# Power.net
KiCad netlist of a schematic drawn in Altium Designer
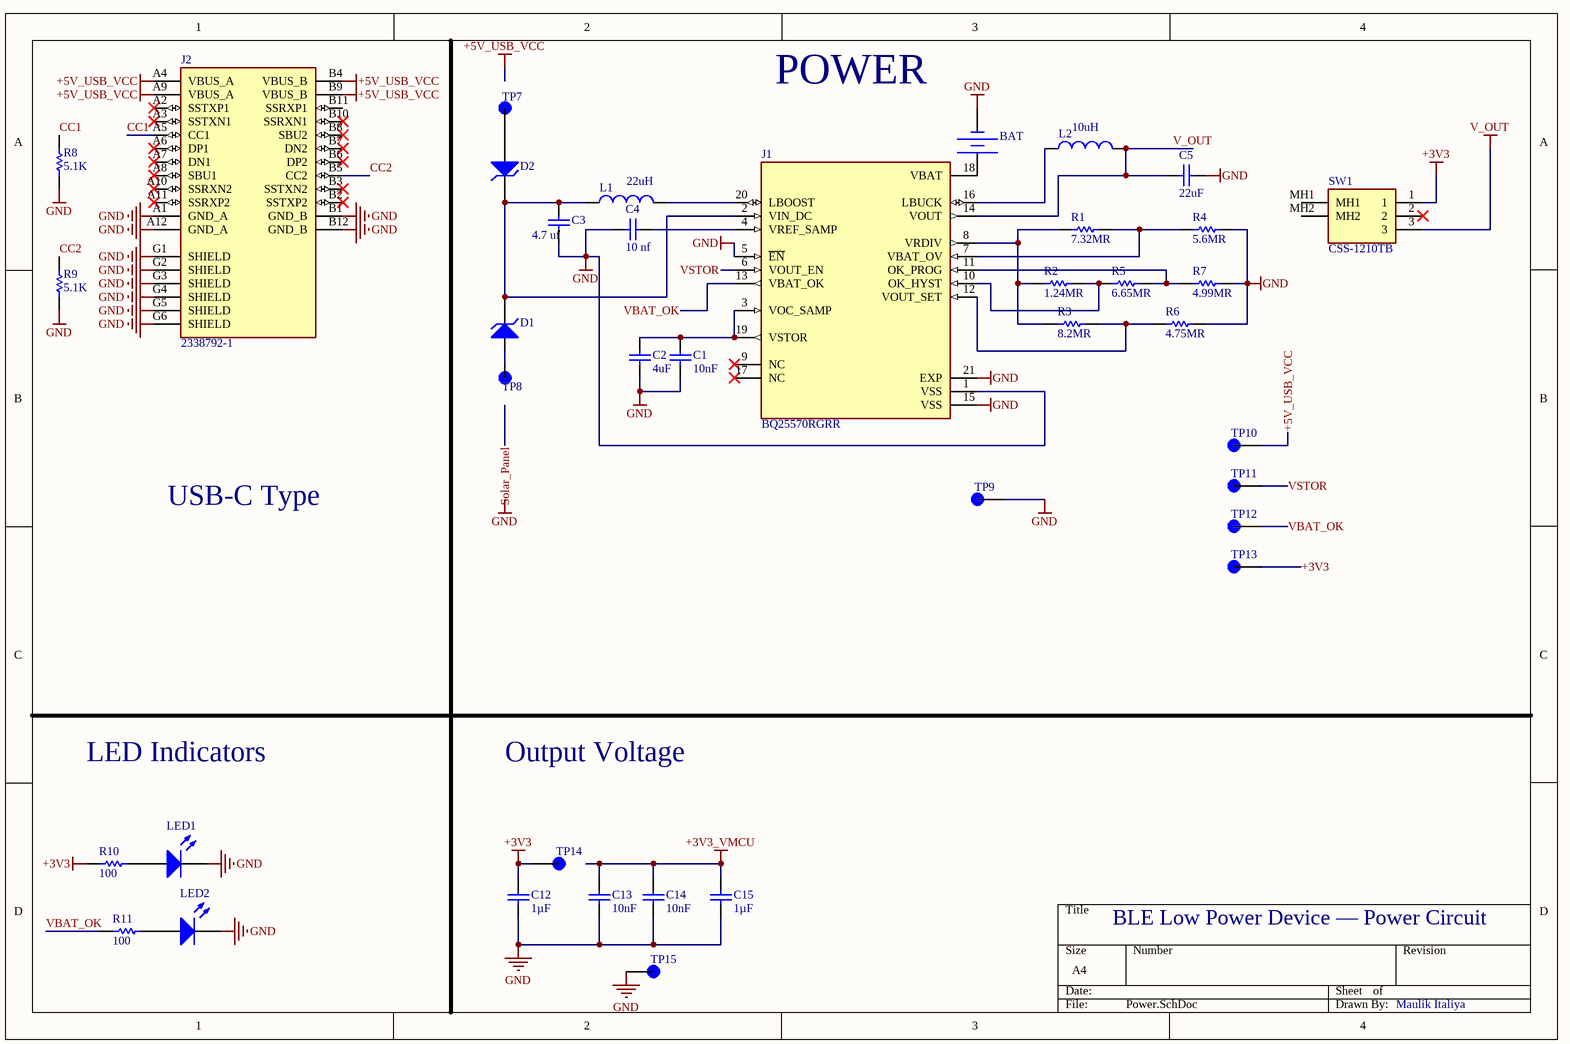
[diagram p0: Power.SchDoc]

(export (version "E")
  (design (tool "Eeschema 10.0.6"))
  (components
    (comp (ref "BAT")
      (value "Constant Voltage Source")
      (libsource (lib "Simulation Generic Components") (part "Battery"))
    )
    (comp (ref "C1")
      (value "10nF")
      (description "Capacitor")
      (libsource (lib "Simulation Generic Components") (part "Capacitor"))
    )
    (comp (ref "C2")
      (value "4uF")
      (description "Capacitor")
      (libsource (lib "Simulation Generic Components") (part "Capacitor"))
    )
    (comp (ref "C3")
      (value "4.7 uf")
      (description "Capacitor")
      (libsource (lib "Simulation Generic Components") (part "Capacitor"))
    )
    (comp (ref "C4")
      (value "10 nf")
      (description "Capacitor")
      (libsource (lib "Simulation Generic Components") (part "Capacitor"))
    )
    (comp (ref "C5")
      (value "22uF")
      (description "Capacitor")
      (libsource (lib "Simulation Generic Components") (part "Capacitor"))
    )
    (comp (ref "C12")
      (value "1µF")
      (description "Capacitor")
      (libsource (lib "Simulation Generic Components") (part "Capacitor"))
    )
    (comp (ref "C13")
      (value "10nF")
      (description "Capacitor")
      (libsource (lib "Simulation Generic Components") (part "Capacitor"))
    )
    (comp (ref "C14")
      (value "10nF")
      (description "Capacitor")
      (libsource (lib "Simulation Generic Components") (part "Capacitor"))
    )
    (comp (ref "C15")
      (value "1µF")
      (description "Capacitor")
      (libsource (lib "Simulation Generic Components") (part "Capacitor"))
    )
    (comp (ref "D1")
      (value "Zener Diode")
      (libsource (lib "Simulation Generic Components") (part "Zener Diode"))
    )
    (comp (ref "D2")
      (value "Zener Diode")
      (libsource (lib "Simulation Generic Components") (part "Zener Diode"))
    )
    (comp (ref "J1")
      (value "BQ25570RGRR")
      (footprint "QFN50P350X350X100-21N")
      (description "Ultra Low power Harvester power Management IC with boost charger, and Nanopower Buck Converter")
      (fields (field (name "MF") "Texas Instruments"))
      (libsource (lib "BQ25570RGRR") (part "BQ25570RGRR"))
    )
    (comp (ref "J2")
      (value "2338792-1")
      (footprint "TE_2338792-1")
      (description "USB TYPE C 3.1 CONN REV TOP MOUNT CH1.6")
      (fields (field (name "MF") "TE Connectivity"))
      (libsource (lib "2338792-1") (part "2338792-1"))
    )
    (comp (ref "L1")
      (value "22uH")
      (description "Inductor")
      (libsource (lib "Simulation Generic Components") (part "Inductor"))
    )
    (comp (ref "L2")
      (value "10uH")
      (description "Inductor")
      (libsource (lib "Simulation Generic Components") (part "Inductor"))
    )
    (comp (ref "LED1")
      (value "Green")
      (description "Light-Emitting Diode")
      (libsource (lib "Simulation Generic Components") (part "LED"))
    )
    (comp (ref "LED2")
      (value "Light-Emitting Diode")
      (libsource (lib "Simulation Generic Components") (part "LED"))
    )
    (comp (ref "R1")
      (value "7.32MR")
      (description "Resistor")
      (libsource (lib "Simulation Generic Components") (part "Resistor"))
    )
    (comp (ref "R2")
      (value "1.24MR")
      (description "Resistor")
      (libsource (lib "Simulation Generic Components") (part "Resistor"))
    )
    (comp (ref "R3")
      (value "8.2MR")
      (description "Resistor")
      (libsource (lib "Simulation Generic Components") (part "Resistor"))
    )
    (comp (ref "R4")
      (value "5.6MR")
      (description "Resistor")
      (libsource (lib "Simulation Generic Components") (part "Resistor"))
    )
    (comp (ref "R5")
      (value "6.65MR")
      (description "Resistor")
      (libsource (lib "Simulation Generic Components") (part "Resistor"))
    )
    (comp (ref "R6")
      (value "4.75MR")
      (description "Resistor")
      (libsource (lib "Simulation Generic Components") (part "Resistor"))
    )
    (comp (ref "R7")
      (value "4.99MR")
      (description "Resistor")
      (libsource (lib "Simulation Generic Components") (part "Resistor"))
    )
    (comp (ref "R8")
      (value "5.1K")
      (description "Resistor")
      (libsource (lib "Simulation Generic Components") (part "Resistor"))
    )
    (comp (ref "R9")
      (value "5.1K")
      (description "Resistor")
      (libsource (lib "Simulation Generic Components") (part "Resistor"))
    )
    (comp (ref "R10")
      (value "100")
      (description "Resistor")
      (libsource (lib "Simulation Generic Components") (part "Resistor"))
    )
    (comp (ref "R11")
      (value "100")
      (description "Resistor")
      (libsource (lib "Simulation Generic Components") (part "Resistor"))
    )
    (comp (ref "SW1")
      (value "CSS-1210TB")
      (footprint "CSS1210TB")
      (description "SWITCH SLIDE SPDT 100MA 12V")
      (fields (field (name "MOUSER PART NUMBER") "229-CSS-1210TB"))
      (libsource (lib "CSS-1210TB") (part "CSS-1210TB"))
    )
    (comp (ref "TP7")
      (value "~")
      (footprint "KEYSTONE_5003")
      (fields (field (name "MF") "Keystone Electronics Corp.") (field (name "MP") "5003"))
      (libsource (lib "5003") (part "5003"))
    )
    (comp (ref "TP8")
      (value "~")
      (footprint "KEYSTONE_5003")
      (fields (field (name "MF") "Keystone Electronics Corp.") (field (name "MP") "5003"))
      (libsource (lib "5003") (part "5003"))
    )
    (comp (ref "TP9")
      (value "~")
      (footprint "KEYSTONE_5003")
      (fields (field (name "MF") "Keystone Electronics Corp.") (field (name "MP") "5003"))
      (libsource (lib "5003") (part "5003"))
    )
    (comp (ref "TP10")
      (value "~")
      (footprint "KEYSTONE_5003")
      (fields (field (name "MF") "Keystone Electronics Corp.") (field (name "MP") "5003"))
      (libsource (lib "5003") (part "5003"))
    )
    (comp (ref "TP11")
      (value "~")
      (footprint "KEYSTONE_5003")
      (fields (field (name "MF") "Keystone Electronics Corp.") (field (name "MP") "5003"))
      (libsource (lib "5003") (part "5003"))
    )
    (comp (ref "TP12")
      (value "~")
      (footprint "KEYSTONE_5003")
      (fields (field (name "MF") "Keystone Electronics Corp.") (field (name "MP") "5003"))
      (libsource (lib "5003") (part "5003"))
    )
    (comp (ref "TP13")
      (value "~")
      (footprint "KEYSTONE_5003")
      (fields (field (name "MF") "Keystone Electronics Corp.") (field (name "MP") "5003"))
      (libsource (lib "5003") (part "5003"))
    )
    (comp (ref "TP14")
      (value "~")
      (footprint "KEYSTONE_5003")
      (fields (field (name "MF") "Keystone Electronics Corp.") (field (name "MP") "5003"))
      (libsource (lib "5003") (part "5003"))
    )
    (comp (ref "TP15")
      (value "~")
      (footprint "KEYSTONE_5003")
      (fields (field (name "MF") "Keystone Electronics Corp.") (field (name "MP") "5003"))
      (libsource (lib "5003") (part "5003"))
    )
  )
  (nets
    (net (code "1") (name "+3V3") (class "Default")
      (node (ref "C12") (pin "1") (pinfunction "1_1") (pintype "passive"))
      (node (ref "R10") (pin "2") (pinfunction "2_2") (pintype "passive"))
      (node (ref "SW1") (pin "1") (pinfunction "1_1") (pintype "passive"))
      (node (ref "TP13") (pin "TP") (pinfunction "TP_TP") (pintype "passive"))
      (node (ref "TP14") (pin "TP") (pinfunction "TP_TP") (pintype "passive"))
    )
    (net (code "2") (name "+3V3_VMCU") (class "Default")
      (node (ref "C13") (pin "1") (pinfunction "1_1") (pintype "passive"))
      (node (ref "C14") (pin "1") (pinfunction "1_1") (pintype "passive"))
      (node (ref "C15") (pin "1") (pinfunction "1_1") (pintype "passive"))
    )
    (net (code "3") (name "+5V_USB_VCC") (class "Default")
      (node (ref "J2") (pin "A4") (pinfunction "VBUS_A_A4") (pintype "power_in"))
      (node (ref "J2") (pin "A9") (pinfunction "VBUS_A_A9") (pintype "power_in"))
      (node (ref "J2") (pin "B4") (pinfunction "VBUS_B_B4") (pintype "power_in"))
      (node (ref "J2") (pin "B9") (pinfunction "VBUS_B_B9") (pintype "power_in"))
      (node (ref "TP10") (pin "TP") (pinfunction "TP_TP") (pintype "passive"))
    )
    (net (code "4") (name "/CC1") (class "Default")
      (node (ref "J2") (pin "A5") (pinfunction "CC1_A5") (pintype "bidirectional"))
      (node (ref "R8") (pin "2") (pinfunction "2_2") (pintype "passive"))
    )
    (net (code "5") (name "/CC2") (class "Default")
      (node (ref "J2") (pin "B5") (pinfunction "CC2_B5") (pintype "bidirectional"))
      (node (ref "R9") (pin "2") (pinfunction "2_2") (pintype "passive"))
    )
    (net (code "7") (name "/VBAT_OK") (class "Default")
      (node (ref "J1") (pin "13") (pinfunction "VBAT_OK_13") (pintype "output"))
      (node (ref "R11") (pin "2") (pinfunction "2_2") (pintype "passive"))
      (node (ref "TP12") (pin "TP") (pinfunction "TP_TP") (pintype "passive"))
    )
    (net (code "8") (name "/VSTOR") (class "Default")
      (node (ref "J1") (pin "6") (pinfunction "VOUT_EN_6") (pintype "input"))
      (node (ref "TP11") (pin "TP") (pinfunction "TP_TP") (pintype "passive"))
    )
    (net (code "9") (name "GND") (class "Default")
      (node (ref "BAT") (pin "2") (pinfunction "2_2") (pintype "passive"))
      (node (ref "C1") (pin "1") (pinfunction "1_1") (pintype "passive"))
      (node (ref "C12") (pin "2") (pinfunction "2_2") (pintype "passive"))
      (node (ref "C13") (pin "2") (pinfunction "2_2") (pintype "passive"))
      (node (ref "C14") (pin "2") (pinfunction "2_2") (pintype "passive"))
      (node (ref "C15") (pin "2") (pinfunction "2_2") (pintype "passive"))
      (node (ref "C2") (pin "1") (pinfunction "1_1") (pintype "passive"))
      (node (ref "C3") (pin "1") (pinfunction "1_1") (pintype "passive"))
      (node (ref "C4") (pin "2") (pinfunction "2_2") (pintype "passive"))
      (node (ref "C5") (pin "2") (pinfunction "2_2") (pintype "passive"))
      (node (ref "J1") (pin "1") (pinfunction "VSS_1") (pintype "power_in"))
      (node (ref "J1") (pin "15") (pinfunction "VSS_15") (pintype "power_in"))
      (node (ref "J1") (pin "21") (pinfunction "EXP_21") (pintype "passive"))
      (node (ref "J1") (pin "5") (pinfunction "~{EN}_5") (pintype "input"))
      (node (ref "J2") (pin "A1") (pinfunction "GND_A_A1") (pintype "power_in"))
      (node (ref "J2") (pin "A12") (pinfunction "GND_A_A12") (pintype "power_in"))
      (node (ref "J2") (pin "B1") (pinfunction "GND_B_B1") (pintype "power_in"))
      (node (ref "J2") (pin "B12") (pinfunction "GND_B_B12") (pintype "power_in"))
      (node (ref "J2") (pin "G1") (pinfunction "SHIELD_G1") (pintype "passive"))
      (node (ref "J2") (pin "G2") (pinfunction "SHIELD_G2") (pintype "passive"))
      (node (ref "J2") (pin "G3") (pinfunction "SHIELD_G3") (pintype "passive"))
      (node (ref "J2") (pin "G4") (pinfunction "SHIELD_G4") (pintype "passive"))
      (node (ref "J2") (pin "G5") (pinfunction "SHIELD_G5") (pintype "passive"))
      (node (ref "J2") (pin "G6") (pinfunction "SHIELD_G6") (pintype "passive"))
      (node (ref "LED1") (pin "2") (pinfunction "K_2") (pintype "passive"))
      (node (ref "LED2") (pin "2") (pinfunction "K_2") (pintype "passive"))
      (node (ref "R4") (pin "2") (pinfunction "2_2") (pintype "passive"))
      (node (ref "R6") (pin "2") (pinfunction "2_2") (pintype "passive"))
      (node (ref "R7") (pin "2") (pinfunction "2_2") (pintype "passive"))
      (node (ref "R8") (pin "1") (pinfunction "1_1") (pintype "passive"))
      (node (ref "R9") (pin "1") (pinfunction "1_1") (pintype "passive"))
      (node (ref "TP15") (pin "TP") (pinfunction "TP_TP") (pintype "passive"))
      (node (ref "TP9") (pin "TP") (pinfunction "TP_TP") (pintype "passive"))
    )
    (net (code "10") (name "Net-(D1-A)") (class "Default")
      (node (ref "D1") (pin "1") (pinfunction "A_1") (pintype "passive"))
      (node (ref "TP8") (pin "TP") (pinfunction "TP_TP") (pintype "passive"))
    )
    (net (code "11") (name "Net-(D1-K)") (class "Default")
      (node (ref "C3") (pin "2") (pinfunction "2_2") (pintype "passive"))
      (node (ref "D1") (pin "2") (pinfunction "K_2") (pintype "passive"))
      (node (ref "D2") (pin "2") (pinfunction "K_2") (pintype "passive"))
      (node (ref "J1") (pin "2") (pinfunction "VIN_DC_2") (pintype "input"))
      (node (ref "L1") (pin "1") (pinfunction "1_1") (pintype "passive"))
    )
    (net (code "12") (name "Net-(D2-A)") (class "Default")
      (node (ref "D2") (pin "1") (pinfunction "A_1") (pintype "passive"))
      (node (ref "TP7") (pin "TP") (pinfunction "TP_TP") (pintype "passive"))
    )
    (net (code "13") (name "Net-(J1-LBOOST)") (class "Default")
      (node (ref "J1") (pin "20") (pinfunction "LBOOST_20") (pintype "bidirectional"))
      (node (ref "L1") (pin "2") (pinfunction "2_2") (pintype "passive"))
    )
    (net (code "14") (name "Net-(J1-LBUCK)") (class "Default")
      (node (ref "J1") (pin "16") (pinfunction "LBUCK_16") (pintype "bidirectional"))
      (node (ref "L2") (pin "1") (pinfunction "1_1") (pintype "passive"))
    )
    (net (code "15") (name "Net-(J1-OK_HYST)") (class "Default")
      (node (ref "J1") (pin "10") (pinfunction "OK_HYST_10") (pintype "input"))
      (node (ref "R2") (pin "2") (pinfunction "2_2") (pintype "passive"))
      (node (ref "R5") (pin "1") (pinfunction "1_1") (pintype "passive"))
    )
    (net (code "16") (name "Net-(J1-OK_PROG)") (class "Default")
      (node (ref "J1") (pin "11") (pinfunction "OK_PROG_11") (pintype "input"))
      (node (ref "R5") (pin "2") (pinfunction "2_2") (pintype "passive"))
      (node (ref "R7") (pin "1") (pinfunction "1_1") (pintype "passive"))
    )
    (net (code "17") (name "Net-(J1-VBAT)") (class "Default")
      (node (ref "BAT") (pin "1") (pinfunction "1_1") (pintype "passive"))
      (node (ref "J1") (pin "18") (pinfunction "VBAT_18") (pintype "power_in"))
    )
    (net (code "18") (name "Net-(J1-VBAT_OV)") (class "Default")
      (node (ref "J1") (pin "7") (pinfunction "VBAT_OV_7") (pintype "input"))
      (node (ref "R1") (pin "2") (pinfunction "2_2") (pintype "passive"))
      (node (ref "R4") (pin "1") (pinfunction "1_1") (pintype "passive"))
    )
    (net (code "19") (name "Net-(J1-VOC_SAMP)") (class "Default")
      (node (ref "C1") (pin "2") (pinfunction "2_2") (pintype "passive"))
      (node (ref "C2") (pin "2") (pinfunction "2_2") (pintype "passive"))
      (node (ref "J1") (pin "19") (pinfunction "VSTOR_19") (pintype "output"))
      (node (ref "J1") (pin "3") (pinfunction "VOC_SAMP_3") (pintype "input"))
    )
    (net (code "20") (name "Net-(J1-VOUT_SET)") (class "Default")
      (node (ref "J1") (pin "12") (pinfunction "VOUT_SET_12") (pintype "input"))
      (node (ref "R3") (pin "2") (pinfunction "2_2") (pintype "passive"))
      (node (ref "R6") (pin "1") (pinfunction "1_1") (pintype "passive"))
    )
    (net (code "21") (name "Net-(J1-VRDIV)") (class "Default")
      (node (ref "J1") (pin "8") (pinfunction "VRDIV_8") (pintype "output"))
      (node (ref "R1") (pin "1") (pinfunction "1_1") (pintype "passive"))
      (node (ref "R2") (pin "1") (pinfunction "1_1") (pintype "passive"))
      (node (ref "R3") (pin "1") (pinfunction "1_1") (pintype "passive"))
    )
    (net (code "22") (name "Net-(J1-VREF_SAMP)") (class "Default")
      (node (ref "C4") (pin "1") (pinfunction "1_1") (pintype "passive"))
      (node (ref "J1") (pin "4") (pinfunction "VREF_SAMP_4") (pintype "input"))
    )
    (net (code "23") (name "Net-(LED1-A)") (class "Default")
      (node (ref "LED1") (pin "1") (pinfunction "A_1") (pintype "passive"))
      (node (ref "R10") (pin "1") (pinfunction "1_1") (pintype "passive"))
    )
    (net (code "24") (name "Net-(LED2-A)") (class "Default")
      (node (ref "LED2") (pin "1") (pinfunction "A_1") (pintype "passive"))
      (node (ref "R11") (pin "1") (pinfunction "1_1") (pintype "passive"))
    )
    (net (code "25") (name "V_OUT") (class "Default")
      (node (ref "C5") (pin "1") (pinfunction "1_1") (pintype "passive"))
      (node (ref "J1") (pin "14") (pinfunction "VOUT_14") (pintype "output"))
      (node (ref "L2") (pin "2") (pinfunction "2_2") (pintype "passive"))
      (node (ref "SW1") (pin "3") (pinfunction "3_3") (pintype "passive"))
    )
    (net (code "26") (name "unconnected-(J1-NC-Pad9)") (class "Default")
      (node (ref "J1") (pin "9") (pinfunction "NC_9") (pintype "passive+no_connect"))
    )
    (net (code "27") (name "unconnected-(J1-NC-Pad17)") (class "Default")
      (node (ref "J1") (pin "17") (pinfunction "NC_17") (pintype "passive+no_connect"))
    )
    (net (code "28") (name "unconnected-(J2-DN1-PadA7)") (class "Default")
      (node (ref "J2") (pin "A7") (pinfunction "DN1_A7") (pintype "bidirectional+no_connect"))
    )
    (net (code "29") (name "unconnected-(J2-DN2-PadB7)") (class "Default")
      (node (ref "J2") (pin "B7") (pinfunction "DN2_B7") (pintype "bidirectional+no_connect"))
    )
    (net (code "30") (name "unconnected-(J2-DP1-PadA6)") (class "Default")
      (node (ref "J2") (pin "A6") (pinfunction "DP1_A6") (pintype "bidirectional+no_connect"))
    )
    (net (code "31") (name "unconnected-(J2-DP2-PadB6)") (class "Default")
      (node (ref "J2") (pin "B6") (pinfunction "DP2_B6") (pintype "bidirectional+no_connect"))
    )
    (net (code "32") (name "unconnected-(J2-SBU1-PadA8)") (class "Default")
      (node (ref "J2") (pin "A8") (pinfunction "SBU1_A8") (pintype "bidirectional+no_connect"))
    )
    (net (code "33") (name "unconnected-(J2-SBU2-PadB8)") (class "Default")
      (node (ref "J2") (pin "B8") (pinfunction "SBU2_B8") (pintype "bidirectional+no_connect"))
    )
    (net (code "34") (name "unconnected-(J2-SSRXN1-PadB10)") (class "Default")
      (node (ref "J2") (pin "B10") (pinfunction "SSRXN1_B10") (pintype "bidirectional+no_connect"))
    )
    (net (code "35") (name "unconnected-(J2-SSRXN2-PadA10)") (class "Default")
      (node (ref "J2") (pin "A10") (pinfunction "SSRXN2_A10") (pintype "bidirectional+no_connect"))
    )
    (net (code "36") (name "unconnected-(J2-SSRXP1-PadB11)") (class "Default")
      (node (ref "J2") (pin "B11") (pinfunction "SSRXP1_B11") (pintype "bidirectional"))
    )
    (net (code "37") (name "unconnected-(J2-SSRXP2-PadA11)") (class "Default")
      (node (ref "J2") (pin "A11") (pinfunction "SSRXP2_A11") (pintype "bidirectional+no_connect"))
    )
    (net (code "38") (name "unconnected-(J2-SSTXN1-PadA3)") (class "Default")
      (node (ref "J2") (pin "A3") (pinfunction "SSTXN1_A3") (pintype "bidirectional+no_connect"))
    )
    (net (code "39") (name "unconnected-(J2-SSTXN2-PadB3)") (class "Default")
      (node (ref "J2") (pin "B3") (pinfunction "SSTXN2_B3") (pintype "bidirectional+no_connect"))
    )
    (net (code "40") (name "unconnected-(J2-SSTXP1-PadA2)") (class "Default")
      (node (ref "J2") (pin "A2") (pinfunction "SSTXP1_A2") (pintype "bidirectional+no_connect"))
    )
    (net (code "41") (name "unconnected-(J2-SSTXP2-PadB2)") (class "Default")
      (node (ref "J2") (pin "B2") (pinfunction "SSTXP2_B2") (pintype "bidirectional+no_connect"))
    )
    (net (code "42") (name "unconnected-(SW1-Pad2)") (class "Default")
      (node (ref "SW1") (pin "2") (pinfunction "2_2") (pintype "passive+no_connect"))
    )
    (net (code "43") (name "unconnected-(SW1-PadMH1)") (class "Default")
      (node (ref "SW1") (pin "MH1") (pinfunction "MH1_MH1") (pintype "passive"))
    )
    (net (code "44") (name "unconnected-(SW1-PadMH2)") (class "Default")
      (node (ref "SW1") (pin "MH2") (pinfunction "MH2_MH2") (pintype "passive"))
    )
  )
)
